# schematic_ap_team10.net
KiCad netlist of a schematic drawn in EAGLE
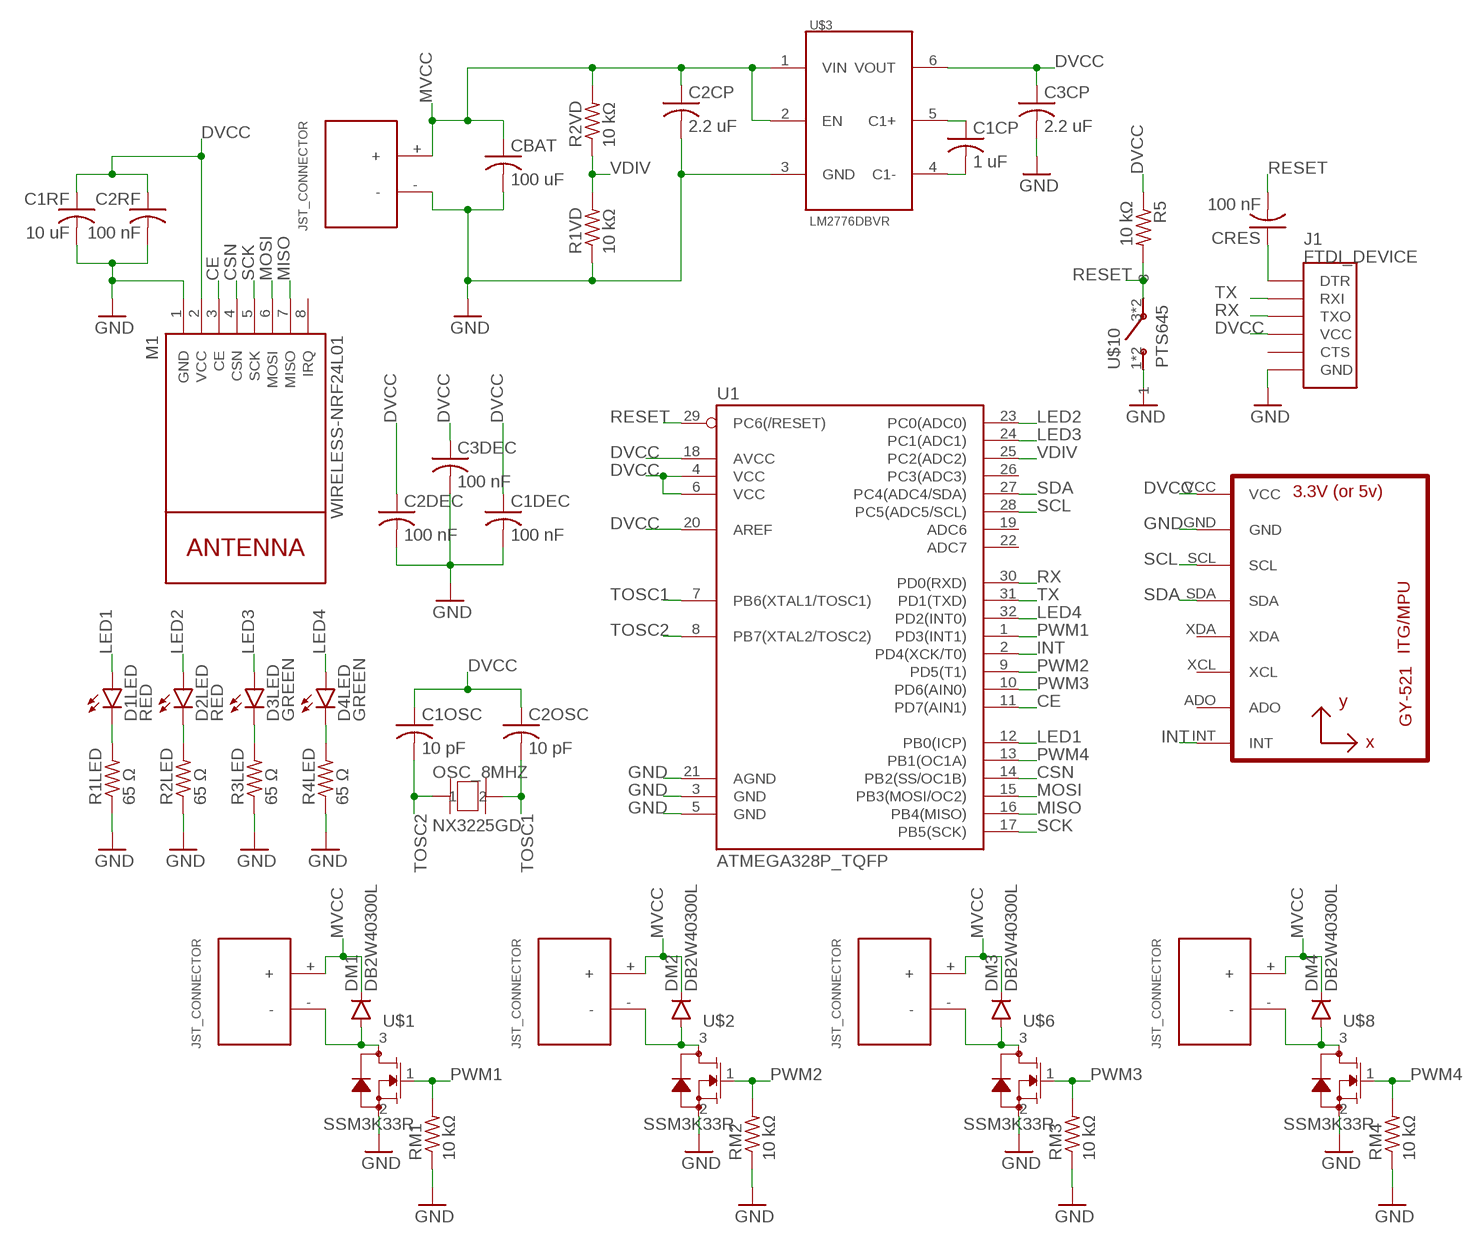
[diagram p0: schematic, sheet 1]

(export (version "E")
  (design (tool "Eeschema 10.0.6"))
  (components
    (comp (ref "C1CP")
      (value "1 uF")
      (footprint "eagle-import:C0603")
      (libsource (lib "eagle-import") (part "C-USC0603"))
    )
    (comp (ref "C1DEC")
      (value "100 nF")
      (footprint "eagle-import:C0603")
      (libsource (lib "eagle-import") (part "C-USC0603"))
    )
    (comp (ref "C1OSC")
      (value "10 pF")
      (footprint "eagle-import:C0603")
      (libsource (lib "eagle-import") (part "C-USC0603"))
    )
    (comp (ref "C1RF")
      (value "10 uF")
      (footprint "eagle-import:C0603")
      (libsource (lib "eagle-import") (part "C-USC0603"))
    )
    (comp (ref "C2CP")
      (value "2.2 uF")
      (footprint "eagle-import:C0603")
      (libsource (lib "eagle-import") (part "C-USC0603"))
    )
    (comp (ref "C2DEC")
      (value "100 nF")
      (footprint "eagle-import:C0603")
      (libsource (lib "eagle-import") (part "C-USC0603"))
    )
    (comp (ref "C2OSC")
      (value "10 pF")
      (footprint "eagle-import:C0603")
      (libsource (lib "eagle-import") (part "C-USC0603"))
    )
    (comp (ref "C2RF")
      (value "100 nF")
      (footprint "eagle-import:C0603")
      (libsource (lib "eagle-import") (part "C-USC0603"))
    )
    (comp (ref "C3CP")
      (value "2.2 uF")
      (footprint "eagle-import:C0603")
      (libsource (lib "eagle-import") (part "C-USC0603"))
    )
    (comp (ref "C3DEC")
      (value "100 nF")
      (footprint "eagle-import:C0603")
      (libsource (lib "eagle-import") (part "C-USC0603"))
    )
    (comp (ref "CBAT")
      (value "100 uF")
      (footprint "eagle-import:C0805")
      (libsource (lib "eagle-import") (part "C-USC0805"))
    )
    (comp (ref "CRES")
      (value "100 nF")
      (footprint "eagle-import:C0603")
      (libsource (lib "eagle-import") (part "C-USC0603"))
    )
    (comp (ref "D1LED")
      (value "RED")
      (footprint "eagle-import:LED-0603")
      (libsource (lib "eagle-import") (part "LED-RED0603"))
    )
    (comp (ref "D2LED")
      (value "RED")
      (footprint "eagle-import:LED-0603")
      (libsource (lib "eagle-import") (part "LED-RED0603"))
    )
    (comp (ref "D3LED")
      (value "GREEN")
      (footprint "eagle-import:LED-0603")
      (libsource (lib "eagle-import") (part "LED-GREEN0603"))
    )
    (comp (ref "D4LED")
      (value "GREEN")
      (footprint "eagle-import:LED-0603")
      (libsource (lib "eagle-import") (part "LED-GREEN0603"))
    )
    (comp (ref "DM1")
      (value "DB2W40300L")
      (footprint "eagle-import:MINI2-F3-B")
      (libsource (lib "eagle-import") (part "DB2W40300L"))
    )
    (comp (ref "DM2")
      (value "DB2W40300L")
      (footprint "eagle-import:MINI2-F3-B")
      (libsource (lib "eagle-import") (part "DB2W40300L"))
    )
    (comp (ref "DM3")
      (value "DB2W40300L")
      (footprint "eagle-import:MINI2-F3-B")
      (libsource (lib "eagle-import") (part "DB2W40300L"))
    )
    (comp (ref "DM4")
      (value "DB2W40300L")
      (footprint "eagle-import:MINI2-F3-B")
      (libsource (lib "eagle-import") (part "DB2W40300L"))
    )
    (comp (ref "J1")
      (value "FTDI_DEVICE")
      (footprint "eagle-import:FTDI_DEVICE_SIDE")
      (libsource (lib "eagle-import") (part "FTDI_DEVICE"))
    )
    (comp (ref "M1")
      (value "WIRELESS-NRF24L01")
      (footprint "eagle-import:WIRELESS-NRF24L01")
      (libsource (lib "eagle-import") (part "WIRELESS-NRF24L01"))
    )
    (comp (ref "OSC_8MHZ")
      (value "NX3225GD")
      (footprint "eagle-import:2-SMD")
      (libsource (lib "eagle-import") (part "NX3225GD"))
    )
    (comp (ref "R1LED")
      (value "65 Ω")
      (footprint "eagle-import:R0603")
      (libsource (lib "eagle-import") (part "R-US_R0603"))
    )
    (comp (ref "R1VD")
      (value "10 kΩ")
      (footprint "eagle-import:R0603")
      (libsource (lib "eagle-import") (part "R-US_R0603"))
    )
    (comp (ref "R2LED")
      (value "65 Ω")
      (footprint "eagle-import:R0603")
      (libsource (lib "eagle-import") (part "R-US_R0603"))
    )
    (comp (ref "R2VD")
      (value "10 kΩ")
      (footprint "eagle-import:R0603")
      (libsource (lib "eagle-import") (part "R-US_R0603"))
    )
    (comp (ref "R3LED")
      (value "65 Ω")
      (footprint "eagle-import:R0603")
      (libsource (lib "eagle-import") (part "R-US_R0603"))
    )
    (comp (ref "R4LED")
      (value "65 Ω")
      (footprint "eagle-import:R0603")
      (libsource (lib "eagle-import") (part "R-US_R0603"))
    )
    (comp (ref "R5")
      (value "10 kΩ")
      (footprint "eagle-import:R0603")
      (libsource (lib "eagle-import") (part "R-US_R0603"))
    )
    (comp (ref "RM1")
      (value "10 kΩ")
      (footprint "eagle-import:R0603")
      (libsource (lib "eagle-import") (part "R-US_R0603"))
    )
    (comp (ref "RM2")
      (value "10 kΩ")
      (footprint "eagle-import:R0603")
      (libsource (lib "eagle-import") (part "R-US_R0603"))
    )
    (comp (ref "RM3")
      (value "10 kΩ")
      (footprint "eagle-import:R0603")
      (libsource (lib "eagle-import") (part "R-US_R0603"))
    )
    (comp (ref "RM4")
      (value "10 kΩ")
      (footprint "eagle-import:R0603")
      (libsource (lib "eagle-import") (part "R-US_R0603"))
    )
    (comp (ref "U$1")
      (value "SSM3K33R")
      (footprint "eagle-import:SOT-23F")
      (libsource (lib "eagle-import") (part "SSM3K33R"))
    )
    (comp (ref "U$2")
      (value "SSM3K33R")
      (footprint "eagle-import:SOT-23F")
      (libsource (lib "eagle-import") (part "SSM3K33R"))
    )
    (comp (ref "U$3")
      (value "LM2776DBVR")
      (footprint "eagle-import:SOT23-5")
      (libsource (lib "eagle-import") (part "LM2776DBVR"))
    )
    (comp (ref "U$4")
      (value "JST_CONNECTOR_FEMALE")
      (footprint "eagle-import:JST_CONNECTOR_FEMALE")
      (libsource (lib "eagle-import") (part "JST_CONNECTOR_FEMALE"))
    )
    (comp (ref "U$5")
      (value "JST_CONNECTOR_FEMALE")
      (footprint "eagle-import:JST_CONNECTOR_FEMALE")
      (libsource (lib "eagle-import") (part "JST_CONNECTOR_FEMALE"))
    )
    (comp (ref "U$6")
      (value "SSM3K33R")
      (footprint "eagle-import:SOT-23F")
      (libsource (lib "eagle-import") (part "SSM3K33R"))
    )
    (comp (ref "U$7")
      (value "JST_CONNECTOR_FEMALE")
      (footprint "eagle-import:JST_CONNECTOR_FEMALE")
      (libsource (lib "eagle-import") (part "JST_CONNECTOR_FEMALE"))
    )
    (comp (ref "U$8")
      (value "SSM3K33R")
      (footprint "eagle-import:SOT-23F")
      (libsource (lib "eagle-import") (part "SSM3K33R"))
    )
    (comp (ref "U$9")
      (value "JST_CONNECTOR_FEMALE")
      (footprint "eagle-import:JST_CONNECTOR_FEMALE")
      (libsource (lib "eagle-import") (part "JST_CONNECTOR_FEMALE"))
    )
    (comp (ref "U$10")
      (value "PTS645")
      (footprint "eagle-import:SOT-35")
      (libsource (lib "eagle-import") (part "PTS645"))
    )
    (comp (ref "U$11")
      (value "JST_CONNECTOR_FEMALE")
      (footprint "eagle-import:JST_CONNECTOR_FEMALE")
      (libsource (lib "eagle-import") (part "JST_CONNECTOR_FEMALE"))
    )
    (comp (ref "U1")
      (value "ATMEGA328P_TQFP")
      (footprint "eagle-import:TQFP32-08")
      (libsource (lib "eagle-import") (part "ATMEGA328P_TQFP"))
    )
    (comp (ref "U2")
      (value "GY-521MPU6050")
      (footprint "eagle-import:GY-521")
      (libsource (lib "eagle-import") (part "GY-521MPU6050"))
    )
  )
  (nets
    (net (code "1") (name "/CE") (class "Default")
      (node (ref "M1") (pin "3") (pinfunction "CE_3") (pintype "bidirectional"))
      (node (ref "U1") (pin "11") (pinfunction "PD7(AIN1)_11") (pintype "bidirectional"))
    )
    (net (code "2") (name "/CSN") (class "Default")
      (node (ref "M1") (pin "4") (pinfunction "CSN_4") (pintype "bidirectional"))
      (node (ref "U1") (pin "14") (pinfunction "PB2(SS/OC1B)_14") (pintype "bidirectional"))
    )
    (net (code "3") (name "/DVCC") (class "Default")
      (node (ref "C1DEC") (pin "1") (pinfunction "1_1") (pintype "passive"))
      (node (ref "C1OSC") (pin "1") (pinfunction "1_1") (pintype "passive"))
      (node (ref "C1RF") (pin "1") (pinfunction "1_1") (pintype "passive"))
      (node (ref "C2DEC") (pin "1") (pinfunction "1_1") (pintype "passive"))
      (node (ref "C2OSC") (pin "1") (pinfunction "1_1") (pintype "passive"))
      (node (ref "C2RF") (pin "1") (pinfunction "1_1") (pintype "passive"))
      (node (ref "C3CP") (pin "1") (pinfunction "1_1") (pintype "passive"))
      (node (ref "C3DEC") (pin "1") (pinfunction "1_1") (pintype "passive"))
      (node (ref "J1") (pin "P$4") (pinfunction "VCC_P$4") (pintype "bidirectional"))
      (node (ref "M1") (pin "2") (pinfunction "VCC_2") (pintype "power_in"))
      (node (ref "R5") (pin "1") (pinfunction "1_1") (pintype "passive"))
      (node (ref "U$3") (pin "6") (pinfunction "VOUT_6") (pintype "bidirectional"))
      (node (ref "U1") (pin "18") (pinfunction "AVCC_18") (pintype "bidirectional"))
      (node (ref "U1") (pin "20") (pinfunction "AREF_20") (pintype "bidirectional"))
      (node (ref "U1") (pin "4") (pinfunction "VCC_4") (pintype "bidirectional"))
      (node (ref "U1") (pin "6") (pinfunction "VCC_6") (pintype "bidirectional"))
      (node (ref "U2") (pin "VCC") (pinfunction "VCC_VCC") (pintype "bidirectional"))
    )
    (net (code "4") (name "/INT") (class "Default")
      (node (ref "U1") (pin "2") (pinfunction "PD4(XCK/T0)_2") (pintype "bidirectional"))
      (node (ref "U2") (pin "INT") (pinfunction "INT_INT") (pintype "bidirectional"))
    )
    (net (code "5") (name "/LED1") (class "Default")
      (node (ref "D1LED") (pin "A") (pinfunction "A_A") (pintype "passive"))
      (node (ref "U1") (pin "12") (pinfunction "PB0(ICP)_12") (pintype "bidirectional"))
    )
    (net (code "6") (name "/LED2") (class "Default")
      (node (ref "D2LED") (pin "A") (pinfunction "A_A") (pintype "passive"))
      (node (ref "U1") (pin "23") (pinfunction "PC0(ADC0)_23") (pintype "bidirectional"))
    )
    (net (code "7") (name "/LED3") (class "Default")
      (node (ref "D3LED") (pin "A") (pinfunction "A_A") (pintype "passive"))
      (node (ref "U1") (pin "24") (pinfunction "PC1(ADC1)_24") (pintype "bidirectional"))
    )
    (net (code "8") (name "/LED4") (class "Default")
      (node (ref "D4LED") (pin "A") (pinfunction "A_A") (pintype "passive"))
      (node (ref "U1") (pin "32") (pinfunction "PD2(INT0)_32") (pintype "bidirectional"))
    )
    (net (code "9") (name "/MISO") (class "Default")
      (node (ref "M1") (pin "7") (pinfunction "MISO_7") (pintype "bidirectional"))
      (node (ref "U1") (pin "16") (pinfunction "PB4(MISO)_16") (pintype "bidirectional"))
    )
    (net (code "10") (name "/MOSI") (class "Default")
      (node (ref "M1") (pin "6") (pinfunction "MOSI_6") (pintype "bidirectional"))
      (node (ref "U1") (pin "15") (pinfunction "PB3(MOSI/OC2)_15") (pintype "bidirectional"))
    )
    (net (code "11") (name "/MVCC") (class "Default")
      (node (ref "C2CP") (pin "1") (pinfunction "1_1") (pintype "passive"))
      (node (ref "CBAT") (pin "1") (pinfunction "1_1") (pintype "passive"))
      (node (ref "DM1") (pin "NEG") (pinfunction "GPIN_NEG") (pintype "passive"))
      (node (ref "DM2") (pin "NEG") (pinfunction "GPIN_NEG") (pintype "passive"))
      (node (ref "DM3") (pin "NEG") (pinfunction "GPIN_NEG") (pintype "passive"))
      (node (ref "DM4") (pin "NEG") (pinfunction "GPIN_NEG") (pintype "passive"))
      (node (ref "R2VD") (pin "2") (pinfunction "2_2") (pintype "passive"))
      (node (ref "U$11") (pin "+") (pinfunction "+_+") (pintype "bidirectional"))
      (node (ref "U$3") (pin "1") (pinfunction "VIN_1") (pintype "bidirectional"))
      (node (ref "U$3") (pin "2") (pinfunction "EN_2") (pintype "bidirectional"))
      (node (ref "U$4") (pin "+") (pinfunction "+_+") (pintype "bidirectional"))
      (node (ref "U$5") (pin "+") (pinfunction "+_+") (pintype "bidirectional"))
      (node (ref "U$7") (pin "+") (pinfunction "+_+") (pintype "bidirectional"))
      (node (ref "U$9") (pin "+") (pinfunction "+_+") (pintype "bidirectional"))
    )
    (net (code "12") (name "/PWM1") (class "Default")
      (node (ref "RM1") (pin "2") (pinfunction "2_2") (pintype "passive"))
      (node (ref "U$1") (pin "1") (pinfunction "1_1") (pintype "bidirectional"))
      (node (ref "U1") (pin "1") (pinfunction "PD3(INT1)_1") (pintype "bidirectional"))
    )
    (net (code "13") (name "/PWM2") (class "Default")
      (node (ref "RM2") (pin "2") (pinfunction "2_2") (pintype "passive"))
      (node (ref "U$2") (pin "1") (pinfunction "1_1") (pintype "bidirectional"))
      (node (ref "U1") (pin "9") (pinfunction "PD5(T1)_9") (pintype "bidirectional"))
    )
    (net (code "14") (name "/PWM3") (class "Default")
      (node (ref "RM3") (pin "2") (pinfunction "2_2") (pintype "passive"))
      (node (ref "U$6") (pin "1") (pinfunction "1_1") (pintype "bidirectional"))
      (node (ref "U1") (pin "10") (pinfunction "PD6(AIN0)_10") (pintype "bidirectional"))
    )
    (net (code "15") (name "/PWM4") (class "Default")
      (node (ref "RM4") (pin "2") (pinfunction "2_2") (pintype "passive"))
      (node (ref "U$8") (pin "1") (pinfunction "1_1") (pintype "bidirectional"))
      (node (ref "U1") (pin "13") (pinfunction "PB1(OC1A)_13") (pintype "bidirectional"))
    )
    (net (code "16") (name "/RESET") (class "Default")
      (node (ref "CRES") (pin "2") (pinfunction "2_2") (pintype "passive"))
      (node (ref "R5") (pin "2") (pinfunction "2_2") (pintype "passive"))
      (node (ref "U$10") (pin "3") (pinfunction "3_3") (pintype "bidirectional"))
      (node (ref "U$10") (pin "4") (pinfunction "3_4") (pintype "bidirectional"))
      (node (ref "U1") (pin "29") (pinfunction "PC6(/RESET)_29") (pintype "bidirectional"))
    )
    (net (code "17") (name "/RX") (class "Default")
      (node (ref "J1") (pin "P$3") (pinfunction "TXO_P$3") (pintype "bidirectional"))
      (node (ref "U1") (pin "30") (pinfunction "PD0(RXD)_30") (pintype "bidirectional"))
    )
    (net (code "18") (name "/SCK") (class "Default")
      (node (ref "M1") (pin "5") (pinfunction "SCK_5") (pintype "bidirectional"))
      (node (ref "U1") (pin "17") (pinfunction "PB5(SCK)_17") (pintype "bidirectional"))
    )
    (net (code "19") (name "/SCL") (class "Default")
      (node (ref "U1") (pin "28") (pinfunction "PC5(ADC5/SCL)_28") (pintype "bidirectional"))
      (node (ref "U2") (pin "SCL") (pinfunction "SCL_SCL") (pintype "bidirectional"))
    )
    (net (code "20") (name "/SDA") (class "Default")
      (node (ref "U1") (pin "27") (pinfunction "PC4(ADC4/SDA)_27") (pintype "bidirectional"))
      (node (ref "U2") (pin "SDA") (pinfunction "SDA_SDA") (pintype "bidirectional"))
    )
    (net (code "21") (name "/TOSC1") (class "Default")
      (node (ref "C2OSC") (pin "2") (pinfunction "2_2") (pintype "passive"))
      (node (ref "OSC_8MHZ") (pin "2") (pinfunction "2_2") (pintype "bidirectional"))
      (node (ref "U1") (pin "7") (pinfunction "PB6(XTAL1/TOSC1)_7") (pintype "bidirectional"))
    )
    (net (code "22") (name "/TOSC2") (class "Default")
      (node (ref "C1OSC") (pin "2") (pinfunction "2_2") (pintype "passive"))
      (node (ref "OSC_8MHZ") (pin "1") (pinfunction "1_1") (pintype "bidirectional"))
      (node (ref "U1") (pin "8") (pinfunction "PB7(XTAL2/TOSC2)_8") (pintype "bidirectional"))
    )
    (net (code "23") (name "/TX") (class "Default")
      (node (ref "J1") (pin "P$2") (pinfunction "RXI_P$2") (pintype "bidirectional"))
      (node (ref "U1") (pin "31") (pinfunction "PD1(TXD)_31") (pintype "bidirectional"))
    )
    (net (code "24") (name "/VDIV") (class "Default")
      (node (ref "R1VD") (pin "2") (pinfunction "2_2") (pintype "passive"))
      (node (ref "R2VD") (pin "1") (pinfunction "1_1") (pintype "passive"))
      (node (ref "U1") (pin "25") (pinfunction "PC2(ADC2)_25") (pintype "bidirectional"))
    )
    (net (code "25") (name "GND") (class "Default")
      (node (ref "C1DEC") (pin "2") (pinfunction "2_2") (pintype "passive"))
      (node (ref "C1RF") (pin "2") (pinfunction "2_2") (pintype "passive"))
      (node (ref "C2CP") (pin "2") (pinfunction "2_2") (pintype "passive"))
      (node (ref "C2DEC") (pin "2") (pinfunction "2_2") (pintype "passive"))
      (node (ref "C2RF") (pin "2") (pinfunction "2_2") (pintype "passive"))
      (node (ref "C3CP") (pin "2") (pinfunction "2_2") (pintype "passive"))
      (node (ref "C3DEC") (pin "2") (pinfunction "2_2") (pintype "passive"))
      (node (ref "CBAT") (pin "2") (pinfunction "2_2") (pintype "passive"))
      (node (ref "J1") (pin "P$6") (pinfunction "GND_P$6") (pintype "bidirectional"))
      (node (ref "M1") (pin "1") (pinfunction "GND_1") (pintype "power_in"))
      (node (ref "R1LED") (pin "1") (pinfunction "1_1") (pintype "passive"))
      (node (ref "R1VD") (pin "1") (pinfunction "1_1") (pintype "passive"))
      (node (ref "R2LED") (pin "1") (pinfunction "1_1") (pintype "passive"))
      (node (ref "R3LED") (pin "1") (pinfunction "1_1") (pintype "passive"))
      (node (ref "R4LED") (pin "1") (pinfunction "1_1") (pintype "passive"))
      (node (ref "RM1") (pin "1") (pinfunction "1_1") (pintype "passive"))
      (node (ref "RM2") (pin "1") (pinfunction "1_1") (pintype "passive"))
      (node (ref "RM3") (pin "1") (pinfunction "1_1") (pintype "passive"))
      (node (ref "RM4") (pin "1") (pinfunction "1_1") (pintype "passive"))
      (node (ref "U$1") (pin "2") (pinfunction "2_2") (pintype "bidirectional"))
      (node (ref "U$10") (pin "1") (pinfunction "1_1") (pintype "bidirectional"))
      (node (ref "U$10") (pin "2") (pinfunction "1_2") (pintype "bidirectional"))
      (node (ref "U$11") (pin "-") (pinfunction "-_-") (pintype "bidirectional"))
      (node (ref "U$2") (pin "2") (pinfunction "2_2") (pintype "bidirectional"))
      (node (ref "U$3") (pin "3") (pinfunction "GND_3") (pintype "bidirectional"))
      (node (ref "U$6") (pin "2") (pinfunction "2_2") (pintype "bidirectional"))
      (node (ref "U$8") (pin "2") (pinfunction "2_2") (pintype "bidirectional"))
      (node (ref "U1") (pin "21") (pinfunction "AGND_21") (pintype "bidirectional"))
      (node (ref "U1") (pin "3") (pinfunction "GND_3") (pintype "bidirectional"))
      (node (ref "U1") (pin "5") (pinfunction "GND_5") (pintype "bidirectional"))
      (node (ref "U2") (pin "GND") (pinfunction "GND_GND") (pintype "bidirectional"))
    )
    (net (code "26") (name "Net-(D1LED-PadC)") (class "Default")
      (node (ref "D1LED") (pin "C") (pinfunction "C_C") (pintype "passive"))
      (node (ref "R1LED") (pin "2") (pinfunction "2_2") (pintype "passive"))
    )
    (net (code "27") (name "Net-(D2LED-PadC)") (class "Default")
      (node (ref "D2LED") (pin "C") (pinfunction "C_C") (pintype "passive"))
      (node (ref "R2LED") (pin "2") (pinfunction "2_2") (pintype "passive"))
    )
    (net (code "28") (name "Net-(D3LED-PadC)") (class "Default")
      (node (ref "D3LED") (pin "C") (pinfunction "C_C") (pintype "passive"))
      (node (ref "R3LED") (pin "2") (pinfunction "2_2") (pintype "passive"))
    )
    (net (code "29") (name "Net-(D4LED-PadC)") (class "Default")
      (node (ref "D4LED") (pin "C") (pinfunction "C_C") (pintype "passive"))
      (node (ref "R4LED") (pin "2") (pinfunction "2_2") (pintype "passive"))
    )
    (net (code "30") (name "Net-(DM1-PPIN)") (class "Default")
      (node (ref "DM1") (pin "POS") (pinfunction "PPIN_POS") (pintype "passive"))
      (node (ref "U$1") (pin "3") (pinfunction "3_3") (pintype "bidirectional"))
      (node (ref "U$4") (pin "-") (pinfunction "-_-") (pintype "bidirectional"))
    )
    (net (code "31") (name "Net-(DM2-PPIN)") (class "Default")
      (node (ref "DM2") (pin "POS") (pinfunction "PPIN_POS") (pintype "passive"))
      (node (ref "U$2") (pin "3") (pinfunction "3_3") (pintype "bidirectional"))
      (node (ref "U$5") (pin "-") (pinfunction "-_-") (pintype "bidirectional"))
    )
    (net (code "32") (name "Net-(DM3-PPIN)") (class "Default")
      (node (ref "DM3") (pin "POS") (pinfunction "PPIN_POS") (pintype "passive"))
      (node (ref "U$6") (pin "3") (pinfunction "3_3") (pintype "bidirectional"))
      (node (ref "U$7") (pin "-") (pinfunction "-_-") (pintype "bidirectional"))
    )
    (net (code "33") (name "Net-(DM4-PPIN)") (class "Default")
      (node (ref "DM4") (pin "POS") (pinfunction "PPIN_POS") (pintype "passive"))
      (node (ref "U$8") (pin "3") (pinfunction "3_3") (pintype "bidirectional"))
      (node (ref "U$9") (pin "-") (pinfunction "-_-") (pintype "bidirectional"))
    )
    (net (code "34") (name "Net-(J1-DTR)") (class "Default")
      (node (ref "CRES") (pin "1") (pinfunction "1_1") (pintype "passive"))
      (node (ref "J1") (pin "P$1") (pinfunction "DTR_P$1") (pintype "bidirectional"))
    )
    (net (code "35") (name "Net-(U$3-C1+)") (class "Default")
      (node (ref "C1CP") (pin "1") (pinfunction "1_1") (pintype "passive"))
      (node (ref "U$3") (pin "5") (pinfunction "C1+_5") (pintype "bidirectional"))
    )
    (net (code "36") (name "Net-(U$3-C1-)") (class "Default")
      (node (ref "C1CP") (pin "2") (pinfunction "2_2") (pintype "passive"))
      (node (ref "U$3") (pin "4") (pinfunction "C1-_4") (pintype "bidirectional"))
    )
    (net (code "37") (name "unconnected-(J1-CTS-PadP$5)") (class "Default")
      (node (ref "J1") (pin "P$5") (pinfunction "CTS_P$5") (pintype "bidirectional"))
    )
    (net (code "38") (name "unconnected-(M1-IRQ-Pad8)") (class "Default")
      (node (ref "M1") (pin "8") (pinfunction "IRQ_8") (pintype "bidirectional"))
    )
    (net (code "39") (name "unconnected-(U1-ADC6-Pad19)") (class "Default")
      (node (ref "U1") (pin "19") (pinfunction "ADC6_19") (pintype "bidirectional"))
    )
    (net (code "40") (name "unconnected-(U1-ADC7-Pad22)") (class "Default")
      (node (ref "U1") (pin "22") (pinfunction "ADC7_22") (pintype "bidirectional"))
    )
    (net (code "41") (name "unconnected-(U1-PC3(ADC3)-Pad26)") (class "Default")
      (node (ref "U1") (pin "26") (pinfunction "PC3(ADC3)_26") (pintype "bidirectional"))
    )
    (net (code "42") (name "unconnected-(U2-PadADO)") (class "Default")
      (node (ref "U2") (pin "ADO") (pinfunction "ADO_ADO") (pintype "bidirectional"))
    )
    (net (code "43") (name "unconnected-(U2-PadXCL)") (class "Default")
      (node (ref "U2") (pin "XCL") (pinfunction "XCL_XCL") (pintype "bidirectional"))
    )
    (net (code "44") (name "unconnected-(U2-PadXDA)") (class "Default")
      (node (ref "U2") (pin "XDA") (pinfunction "XDA_XDA") (pintype "bidirectional"))
    )
  )
)
